# nh-4_3-breakout-v0001.net
KiCad netlist of a schematic drawn in EAGLE
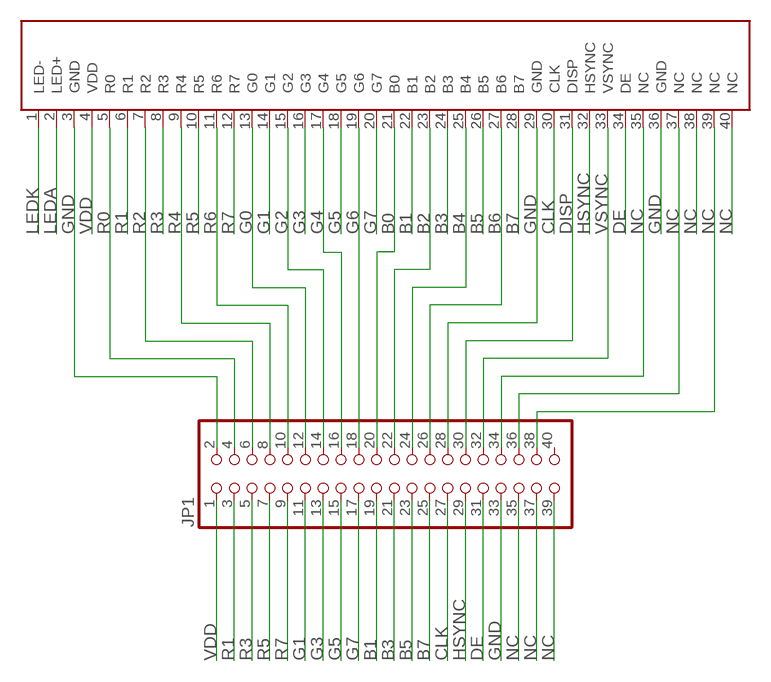
[diagram p0: schematic, sheet 1]
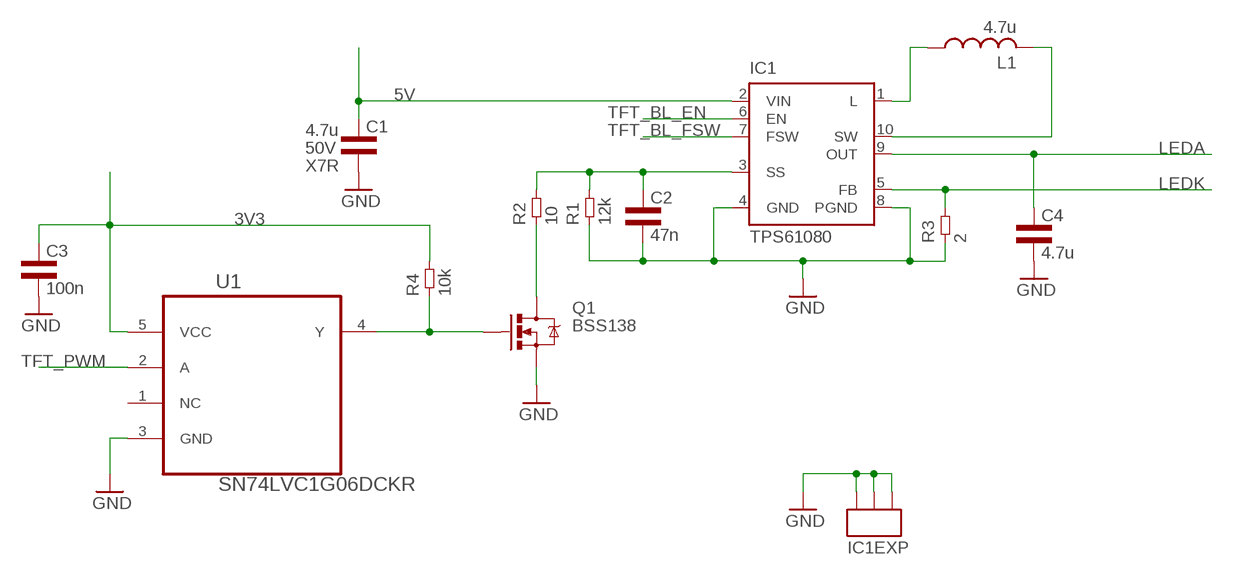
[diagram p1: schematic, sheet 2]

(export (version "E")
  (design (tool "Eeschema 10.0.6"))
  (components
    (comp (ref "C1")
      (value "4.7u")
      (footprint "eagle-import:1210L3")
      (fields (field (name "DIELECTRIC") "X7R") (field (name "VOLTAGE") "50V"))
      (libsource (lib "eagle-import") (part "CAP1210L3"))
    )
    (comp (ref "C2")
      (value "47n")
      (footprint "eagle-import:0603L3")
      (libsource (lib "eagle-import") (part "CAP0603L3"))
    )
    (comp (ref "C3")
      (value "100n")
      (footprint "eagle-import:0603L3")
      (libsource (lib "eagle-import") (part "CAP0603L3"))
    )
    (comp (ref "C4")
      (value "4.7u")
      (footprint "eagle-import:1210L3")
      (libsource (lib "eagle-import") (part "CAP1210L3"))
    )
    (comp (ref "IC1")
      (value "TPS61080")
      (footprint "eagle-import:S-PDSO-N10")
      (fields (field (name "MPN") "TPS61080DRCT"))
      (libsource (lib "eagle-import") (part "TPS61080"))
    )
    (comp (ref "L1")
      (value "4.7u")
      (footprint "eagle-import:RCL_VLCF4018-2")
      (libsource (lib "eagle-import") (part "RCL_L-US"))
    )
    (comp (ref "Q1")
      (value "MOSFET-NCHANNELBSS138")
      (footprint "eagle-import:SOT23")
      (libsource (lib "eagle-import") (part "MOSFET-NCHANNELBSS138"))
    )
    (comp (ref "R1")
      (value "12k")
      (footprint "eagle-import:0603L3")
      (libsource (lib "eagle-import") (part "RES0603L3"))
    )
    (comp (ref "R2")
      (value "10")
      (footprint "eagle-import:0603L3")
      (libsource (lib "eagle-import") (part "RES0603L3"))
    )
    (comp (ref "R3")
      (value "2")
      (footprint "eagle-import:1210L3")
      (libsource (lib "eagle-import") (part "RES1210L3"))
    )
    (comp (ref "R4")
      (value "10k")
      (footprint "eagle-import:0603L3")
      (libsource (lib "eagle-import") (part "RES0603L3"))
    )
    (comp (ref "U1")
      (value "SN74LVC1G06DCKR")
      (footprint "eagle-import:SOT65P210X110-5N")
      (libsource (lib "eagle-import") (part "SN74LVC1G06DCKR"))
    )
    (comp (ref "JP1")
      (value "PINHD-2X20")
      (footprint "eagle-import:2X20")
      (libsource (lib "eagle-import") (part "PINHD-2X20"))
    )
    (comp (ref "U$1")
      (value "NH-4.3")
      (footprint "eagle-import:FPC-40")
      (libsource (lib "eagle-import") (part "NH-4.3"))
    )
  )
  (nets
    (net (code "1") (name "3V3") (class "Default")
      (node (ref "C3") (pin "P$1") (pinfunction "1_P$1") (pintype "bidirectional"))
      (node (ref "R4") (pin "P$2") (pinfunction "2_P$2") (pintype "bidirectional"))
      (node (ref "U1") (pin "5") (pinfunction "VCC_5") (pintype "power_in"))
    )
    (net (code "2") (name "5V") (class "Default")
      (node (ref "C1") (pin "P$1") (pinfunction "1_P$1") (pintype "bidirectional"))
      (node (ref "IC1") (pin "2") (pinfunction "VIN_2") (pintype "input"))
    )
    (net (code "3") (name "B0") (class "Default")
      (node (ref "JP1") (pin "20") (pinfunction "20_20") (pintype "passive"))
      (node (ref "U$1") (pin "21") (pinfunction "B0_21") (pintype "bidirectional"))
    )
    (net (code "4") (name "B1") (class "Default")
      (node (ref "JP1") (pin "19") (pinfunction "19_19") (pintype "passive"))
      (node (ref "U$1") (pin "22") (pinfunction "B1_22") (pintype "bidirectional"))
    )
    (net (code "5") (name "B2") (class "Default")
      (node (ref "JP1") (pin "22") (pinfunction "22_22") (pintype "passive"))
      (node (ref "U$1") (pin "23") (pinfunction "B2_23") (pintype "bidirectional"))
    )
    (net (code "6") (name "B3") (class "Default")
      (node (ref "JP1") (pin "21") (pinfunction "21_21") (pintype "passive"))
      (node (ref "U$1") (pin "24") (pinfunction "B3_24") (pintype "bidirectional"))
    )
    (net (code "7") (name "B4") (class "Default")
      (node (ref "JP1") (pin "24") (pinfunction "24_24") (pintype "passive"))
      (node (ref "U$1") (pin "25") (pinfunction "B4_25") (pintype "bidirectional"))
    )
    (net (code "8") (name "B5") (class "Default")
      (node (ref "JP1") (pin "23") (pinfunction "23_23") (pintype "passive"))
      (node (ref "U$1") (pin "26") (pinfunction "B5_26") (pintype "bidirectional"))
    )
    (net (code "9") (name "B6") (class "Default")
      (node (ref "JP1") (pin "26") (pinfunction "26_26") (pintype "passive"))
      (node (ref "U$1") (pin "27") (pinfunction "B6_27") (pintype "bidirectional"))
    )
    (net (code "10") (name "B7") (class "Default")
      (node (ref "JP1") (pin "25") (pinfunction "25_25") (pintype "passive"))
      (node (ref "U$1") (pin "28") (pinfunction "B7_28") (pintype "bidirectional"))
    )
    (net (code "11") (name "CLK") (class "Default")
      (node (ref "JP1") (pin "27") (pinfunction "27_27") (pintype "passive"))
      (node (ref "U$1") (pin "30") (pinfunction "CLK_30") (pintype "bidirectional"))
    )
    (net (code "12") (name "DE") (class "Default")
      (node (ref "JP1") (pin "31") (pinfunction "31_31") (pintype "passive"))
      (node (ref "U$1") (pin "34") (pinfunction "DE_34") (pintype "bidirectional"))
    )
    (net (code "13") (name "DISP") (class "Default")
      (node (ref "JP1") (pin "30") (pinfunction "30_30") (pintype "passive"))
      (node (ref "U$1") (pin "31") (pinfunction "DISP_31") (pintype "bidirectional"))
    )
    (net (code "14") (name "G0") (class "Default")
      (node (ref "JP1") (pin "12") (pinfunction "12_12") (pintype "passive"))
      (node (ref "U$1") (pin "13") (pinfunction "G0_13") (pintype "bidirectional"))
    )
    (net (code "15") (name "G1") (class "Default")
      (node (ref "JP1") (pin "11") (pinfunction "11_11") (pintype "passive"))
      (node (ref "U$1") (pin "14") (pinfunction "G1_14") (pintype "bidirectional"))
    )
    (net (code "16") (name "G2") (class "Default")
      (node (ref "JP1") (pin "14") (pinfunction "14_14") (pintype "passive"))
      (node (ref "U$1") (pin "15") (pinfunction "G2_15") (pintype "bidirectional"))
    )
    (net (code "17") (name "G3") (class "Default")
      (node (ref "JP1") (pin "13") (pinfunction "13_13") (pintype "passive"))
      (node (ref "U$1") (pin "16") (pinfunction "G3_16") (pintype "bidirectional"))
    )
    (net (code "18") (name "G4") (class "Default")
      (node (ref "JP1") (pin "16") (pinfunction "16_16") (pintype "passive"))
      (node (ref "U$1") (pin "17") (pinfunction "G4_17") (pintype "bidirectional"))
    )
    (net (code "19") (name "G5") (class "Default")
      (node (ref "JP1") (pin "15") (pinfunction "15_15") (pintype "passive"))
      (node (ref "U$1") (pin "18") (pinfunction "G5_18") (pintype "bidirectional"))
    )
    (net (code "20") (name "G6") (class "Default")
      (node (ref "JP1") (pin "18") (pinfunction "18_18") (pintype "passive"))
      (node (ref "U$1") (pin "19") (pinfunction "G6_19") (pintype "bidirectional"))
    )
    (net (code "21") (name "G7") (class "Default")
      (node (ref "JP1") (pin "17") (pinfunction "17_17") (pintype "passive"))
      (node (ref "U$1") (pin "20") (pinfunction "G7_20") (pintype "bidirectional"))
    )
    (net (code "22") (name "GND") (class "Default")
      (node (ref "C1") (pin "P$2") (pinfunction "2_P$2") (pintype "bidirectional"))
      (node (ref "C2") (pin "P$2") (pinfunction "2_P$2") (pintype "bidirectional"))
      (node (ref "C3") (pin "P$2") (pinfunction "2_P$2") (pintype "bidirectional"))
      (node (ref "C4") (pin "P$2") (pinfunction "2_P$2") (pintype "bidirectional"))
      (node (ref "IC1") (pin "4") (pinfunction "GND_4") (pintype "power_in"))
      (node (ref "IC1") (pin "8") (pinfunction "PGND_8") (pintype "input"))
      (node (ref "IC1") (pin "PP") (pinfunction "EXP_PP") (pintype "input"))
      (node (ref "IC1") (pin "PP@1") (pinfunction "EXP_PP@1") (pintype "input"))
      (node (ref "IC1") (pin "PP@2") (pinfunction "EXP_PP@2") (pintype "input"))
      (node (ref "JP1") (pin "2") (pinfunction "2_2") (pintype "passive"))
      (node (ref "JP1") (pin "28") (pinfunction "28_28") (pintype "passive"))
      (node (ref "JP1") (pin "33") (pinfunction "33_33") (pintype "passive"))
      (node (ref "Q1") (pin "2") (pinfunction "S_2") (pintype "passive"))
      (node (ref "R1") (pin "P$1") (pinfunction "1_P$1") (pintype "bidirectional"))
      (node (ref "R3") (pin "P$1") (pinfunction "1_P$1") (pintype "bidirectional"))
      (node (ref "U$1") (pin "29") (pinfunction "GND_29") (pintype "bidirectional"))
      (node (ref "U$1") (pin "3") (pinfunction "GND_3") (pintype "bidirectional"))
      (node (ref "U$1") (pin "36") (pinfunction "GND_36") (pintype "bidirectional"))
      (node (ref "U1") (pin "3") (pinfunction "GND_3") (pintype "passive"))
    )
    (net (code "23") (name "HSYNC") (class "Default")
      (node (ref "JP1") (pin "29") (pinfunction "29_29") (pintype "passive"))
      (node (ref "U$1") (pin "32") (pinfunction "HSYNC_32") (pintype "bidirectional"))
    )
    (net (code "24") (name "LEDA") (class "Default")
      (node (ref "C4") (pin "P$1") (pinfunction "1_P$1") (pintype "bidirectional"))
      (node (ref "IC1") (pin "9") (pinfunction "OUT_9") (pintype "output"))
      (node (ref "U$1") (pin "2") (pinfunction "LED+_2") (pintype "bidirectional"))
    )
    (net (code "25") (name "LEDK") (class "Default")
      (node (ref "IC1") (pin "5") (pinfunction "FB_5") (pintype "input"))
      (node (ref "R3") (pin "P$2") (pinfunction "2_P$2") (pintype "bidirectional"))
      (node (ref "U$1") (pin "1") (pinfunction "LED-_1") (pintype "bidirectional"))
    )
    (net (code "26") (name "NC") (class "Default")
      (node (ref "JP1") (pin "34") (pinfunction "34_34") (pintype "passive"))
      (node (ref "JP1") (pin "35") (pinfunction "35_35") (pintype "passive"))
      (node (ref "JP1") (pin "36") (pinfunction "36_36") (pintype "passive"))
      (node (ref "JP1") (pin "37") (pinfunction "37_37") (pintype "passive"))
      (node (ref "JP1") (pin "38") (pinfunction "38_38") (pintype "passive"))
      (node (ref "JP1") (pin "39") (pinfunction "39_39") (pintype "passive"))
      (node (ref "U$1") (pin "35") (pinfunction "NC_35") (pintype "bidirectional"))
      (node (ref "U$1") (pin "37") (pinfunction "NC_37") (pintype "bidirectional"))
      (node (ref "U$1") (pin "38") (pinfunction "NC_38") (pintype "bidirectional"))
      (node (ref "U$1") (pin "39") (pinfunction "NC_39") (pintype "bidirectional"))
      (node (ref "U$1") (pin "40") (pinfunction "NC_40") (pintype "bidirectional"))
    )
    (net (code "27") (name "Net-(C2-1)") (class "Default")
      (node (ref "C2") (pin "P$1") (pinfunction "1_P$1") (pintype "bidirectional"))
      (node (ref "IC1") (pin "3") (pinfunction "SS_3") (pintype "input"))
      (node (ref "R1") (pin "P$2") (pinfunction "2_P$2") (pintype "bidirectional"))
      (node (ref "R2") (pin "P$2") (pinfunction "2_P$2") (pintype "bidirectional"))
    )
    (net (code "28") (name "Net-(IC1B-L)") (class "Default")
      (node (ref "IC1") (pin "1") (pinfunction "L_1") (pintype "passive"))
      (node (ref "L1") (pin "1") (pinfunction "1_1") (pintype "passive"))
    )
    (net (code "29") (name "Net-(IC1B-SW)") (class "Default")
      (node (ref "IC1") (pin "10") (pinfunction "SW_10") (pintype "passive"))
      (node (ref "L1") (pin "2") (pinfunction "2_2") (pintype "passive"))
    )
    (net (code "30") (name "Net-(Q1-D)") (class "Default")
      (node (ref "Q1") (pin "3") (pinfunction "D_3") (pintype "passive"))
      (node (ref "R2") (pin "P$1") (pinfunction "1_P$1") (pintype "bidirectional"))
    )
    (net (code "31") (name "Net-(Q1-G)") (class "Default")
      (node (ref "Q1") (pin "1") (pinfunction "G_1") (pintype "passive"))
      (node (ref "R4") (pin "P$1") (pinfunction "1_P$1") (pintype "bidirectional"))
      (node (ref "U1") (pin "4") (pinfunction "Y_4") (pintype "output"))
    )
    (net (code "32") (name "R0") (class "Default")
      (node (ref "JP1") (pin "4") (pinfunction "4_4") (pintype "passive"))
      (node (ref "U$1") (pin "5") (pinfunction "R0_5") (pintype "bidirectional"))
    )
    (net (code "33") (name "R1") (class "Default")
      (node (ref "JP1") (pin "3") (pinfunction "3_3") (pintype "passive"))
      (node (ref "U$1") (pin "6") (pinfunction "R1_6") (pintype "bidirectional"))
    )
    (net (code "34") (name "R2") (class "Default")
      (node (ref "JP1") (pin "6") (pinfunction "6_6") (pintype "passive"))
      (node (ref "U$1") (pin "7") (pinfunction "R2_7") (pintype "bidirectional"))
    )
    (net (code "35") (name "R3") (class "Default")
      (node (ref "JP1") (pin "5") (pinfunction "5_5") (pintype "passive"))
      (node (ref "U$1") (pin "8") (pinfunction "R3_8") (pintype "bidirectional"))
    )
    (net (code "36") (name "R4") (class "Default")
      (node (ref "JP1") (pin "8") (pinfunction "8_8") (pintype "passive"))
      (node (ref "U$1") (pin "9") (pinfunction "R4_9") (pintype "bidirectional"))
    )
    (net (code "37") (name "R5") (class "Default")
      (node (ref "JP1") (pin "7") (pinfunction "7_7") (pintype "passive"))
      (node (ref "U$1") (pin "10") (pinfunction "R5_10") (pintype "bidirectional"))
    )
    (net (code "38") (name "R6") (class "Default")
      (node (ref "JP1") (pin "10") (pinfunction "10_10") (pintype "passive"))
      (node (ref "U$1") (pin "11") (pinfunction "R6_11") (pintype "bidirectional"))
    )
    (net (code "39") (name "R7") (class "Default")
      (node (ref "JP1") (pin "9") (pinfunction "9_9") (pintype "passive"))
      (node (ref "U$1") (pin "12") (pinfunction "R7_12") (pintype "bidirectional"))
    )
    (net (code "40") (name "TFT_BL_EN") (class "Default")
      (node (ref "IC1") (pin "6") (pinfunction "EN_6") (pintype "input"))
    )
    (net (code "41") (name "TFT_BL_FSW") (class "Default")
      (node (ref "IC1") (pin "7") (pinfunction "FSW_7") (pintype "input"))
    )
    (net (code "42") (name "TFT_PWM") (class "Default")
      (node (ref "U1") (pin "2") (pinfunction "A_2") (pintype "input"))
    )
    (net (code "43") (name "VDD") (class "Default")
      (node (ref "JP1") (pin "1") (pinfunction "1_1") (pintype "passive"))
      (node (ref "U$1") (pin "4") (pinfunction "VDD_4") (pintype "bidirectional"))
    )
    (net (code "44") (name "VSYNC") (class "Default")
      (node (ref "JP1") (pin "32") (pinfunction "32_32") (pintype "passive"))
      (node (ref "U$1") (pin "33") (pinfunction "VSYNC_33") (pintype "bidirectional"))
    )
    (net (code "45") (name "unconnected-(JP1-Pad40)") (class "Default")
      (node (ref "JP1") (pin "40") (pinfunction "40_40") (pintype "passive"))
    )
    (net (code "46") (name "unconnected-(U1-NC-Pad1)") (class "Default")
      (node (ref "U1") (pin "1") (pinfunction "NC_1") (pintype "no_connect"))
    )
  )
)
